# polarshield3_0b.net
KiCad netlist of a schematic drawn in EAGLE
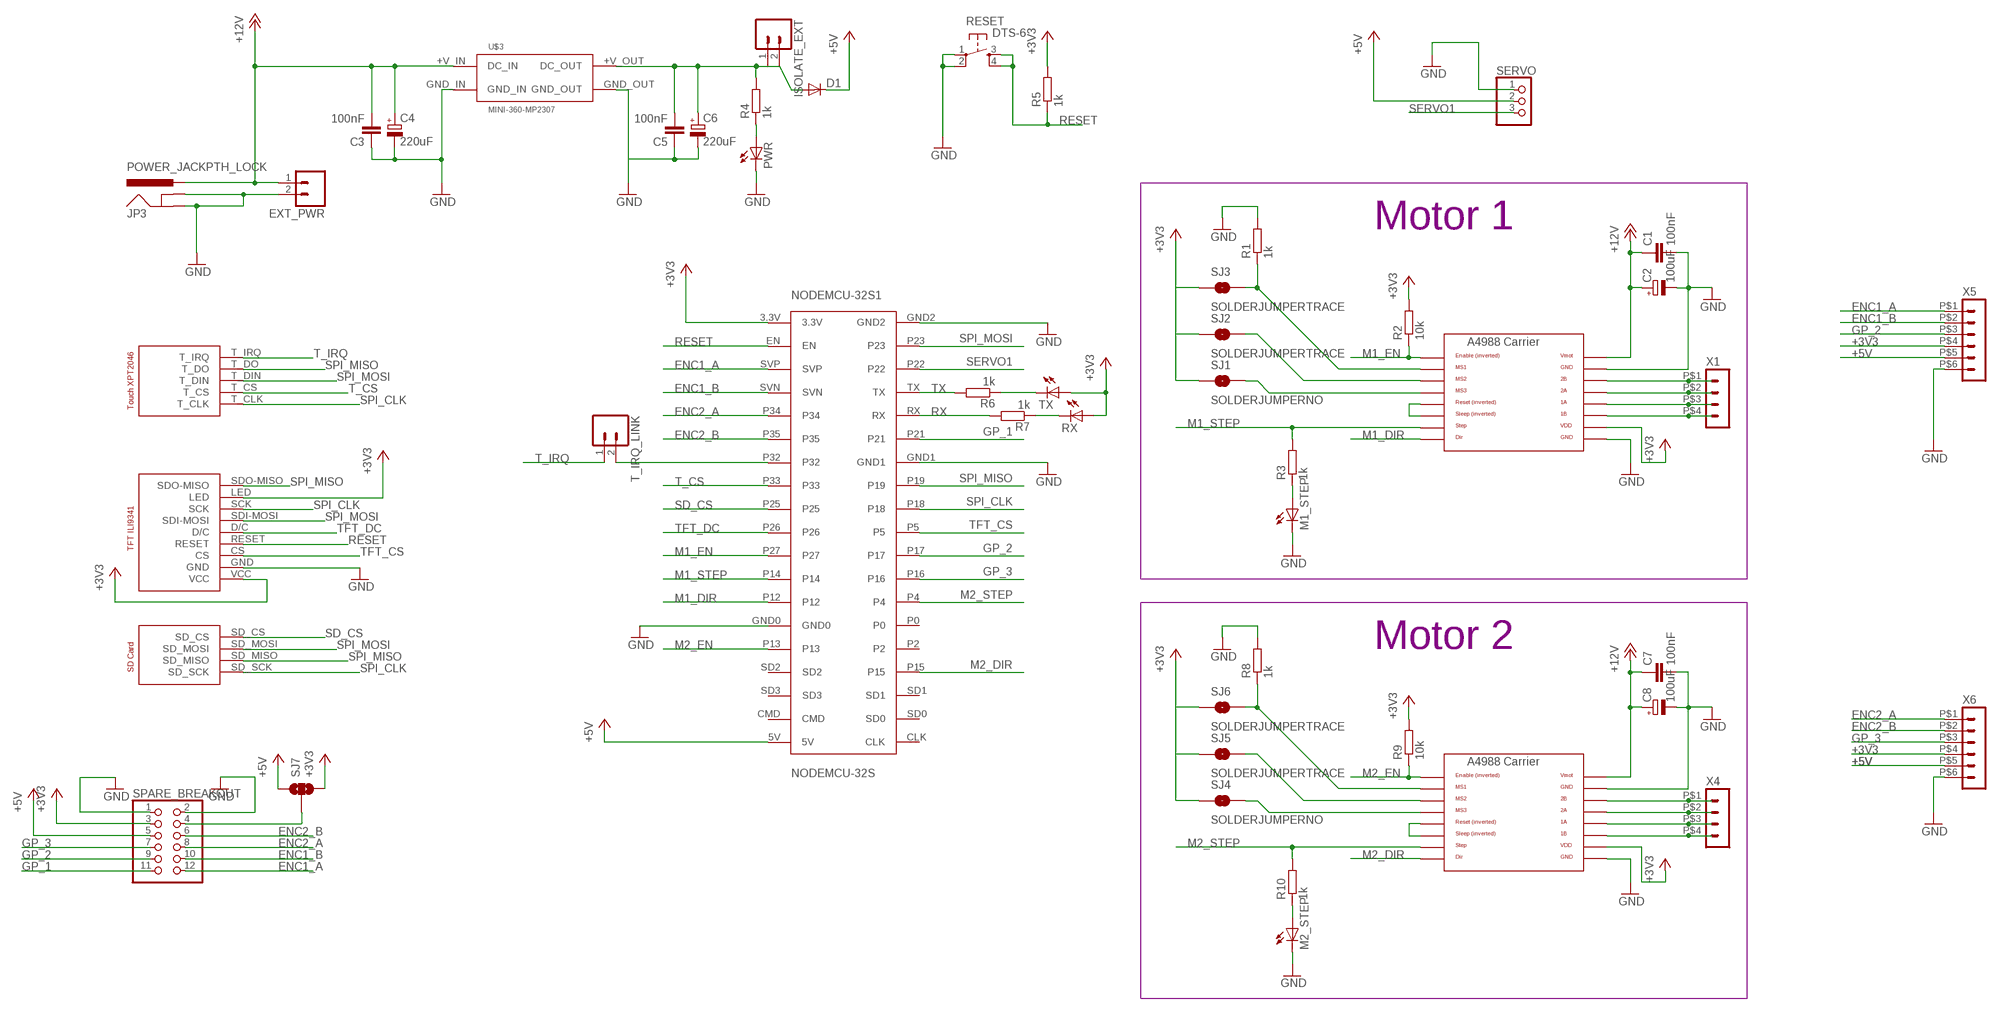
[diagram p0: schematic, sheet 1]

(export (version "E")
  (design (tool "Eeschema 10.0.6"))
  (components
    (comp (ref "C1")
      (value "100nF")
      (footprint "eagle-import:C0805")
      (libsource (lib "eagle-import") (part "C-EUC0805"))
    )
    (comp (ref "C2")
      (value "100uF")
      (footprint "eagle-import:153CLV-0605")
      (libsource (lib "eagle-import") (part "CPOL-EU153CLV-0605"))
    )
    (comp (ref "C3")
      (value "100nF")
      (footprint "eagle-import:C0805")
      (libsource (lib "eagle-import") (part "C-EUC0805"))
    )
    (comp (ref "C4")
      (value "220uF")
      (footprint "eagle-import:153CLV-0605")
      (libsource (lib "eagle-import") (part "CPOL-EU153CLV-0605"))
    )
    (comp (ref "C5")
      (value "100nF")
      (footprint "eagle-import:C0805")
      (libsource (lib "eagle-import") (part "C-EUC0805"))
    )
    (comp (ref "C6")
      (value "220uF")
      (footprint "eagle-import:153CLV-0605")
      (libsource (lib "eagle-import") (part "CPOL-EU153CLV-0605"))
    )
    (comp (ref "C7")
      (value "100nF")
      (footprint "eagle-import:C0805")
      (libsource (lib "eagle-import") (part "C-EUC0805"))
    )
    (comp (ref "C8")
      (value "100uF")
      (footprint "eagle-import:153CLV-0605")
      (libsource (lib "eagle-import") (part "CPOL-EU153CLV-0605"))
    )
    (comp (ref "D1")
      (value "DIODE-DO214BA")
      (footprint "eagle-import:DO214BA")
      (libsource (lib "eagle-import") (part "DIODE-DO214BA"))
    )
    (comp (ref "EXT_PWR")
      (value "M02PTH")
      (footprint "eagle-import:1X02")
      (libsource (lib "eagle-import") (part "M02PTH"))
    )
    (comp (ref "ISOLATE_EXT")
      (value "M02PTH")
      (footprint "eagle-import:1X02")
      (libsource (lib "eagle-import") (part "M02PTH"))
    )
    (comp (ref "JP3")
      (value "POWER_JACKPTH_LOCK")
      (footprint "eagle-import:POWER_JACK_PTH_LOCK")
      (libsource (lib "eagle-import") (part "POWER_JACKPTH_LOCK"))
    )
    (comp (ref "M1_STEP")
      (value "LEDCHIPLED_0805")
      (footprint "eagle-import:CHIPLED_0805")
      (libsource (lib "eagle-import") (part "LEDCHIPLED_0805"))
    )
    (comp (ref "M2_STEP")
      (value "LEDCHIPLED_0805")
      (footprint "eagle-import:CHIPLED_0805")
      (libsource (lib "eagle-import") (part "LEDCHIPLED_0805"))
    )
    (comp (ref "MOTOR_1")
      (value "A4988BREAKOUT")
      (footprint "eagle-import:A4988BREAKOUT")
      (libsource (lib "eagle-import") (part "A4988BREAKOUT"))
    )
    (comp (ref "MOTOR_2")
      (value "A4988BREAKOUT")
      (footprint "eagle-import:A4988BREAKOUT")
      (libsource (lib "eagle-import") (part "A4988BREAKOUT"))
    )
    (comp (ref "NODEMCU-32S1")
      (value "NODEMCU-32S")
      (footprint "eagle-import:NODEMCU-32S")
      (libsource (lib "eagle-import") (part "NODEMCU-32S"))
    )
    (comp (ref "PWR")
      (value "LEDCHIPLED_0805")
      (footprint "eagle-import:CHIPLED_0805")
      (libsource (lib "eagle-import") (part "LEDCHIPLED_0805"))
    )
    (comp (ref "R1")
      (value "1k")
      (footprint "eagle-import:M0805")
      (libsource (lib "eagle-import") (part "R-EU_M0805"))
    )
    (comp (ref "R2")
      (value "10k")
      (footprint "eagle-import:M0805")
      (libsource (lib "eagle-import") (part "R-EU_M0805"))
    )
    (comp (ref "R3")
      (value "1k")
      (footprint "eagle-import:M0805")
      (libsource (lib "eagle-import") (part "R-EU_M0805"))
    )
    (comp (ref "R4")
      (value "1k")
      (footprint "eagle-import:M0805")
      (libsource (lib "eagle-import") (part "R-EU_M0805"))
    )
    (comp (ref "R5")
      (value "1k")
      (footprint "eagle-import:M0805")
      (libsource (lib "eagle-import") (part "R-EU_M0805"))
    )
    (comp (ref "R6")
      (value "1k")
      (footprint "eagle-import:M0805")
      (libsource (lib "eagle-import") (part "R-EU_M0805"))
    )
    (comp (ref "R7")
      (value "1k")
      (footprint "eagle-import:M0805")
      (libsource (lib "eagle-import") (part "R-EU_M0805"))
    )
    (comp (ref "R8")
      (value "1k")
      (footprint "eagle-import:M0805")
      (libsource (lib "eagle-import") (part "R-EU_M0805"))
    )
    (comp (ref "R9")
      (value "10k")
      (footprint "eagle-import:M0805")
      (libsource (lib "eagle-import") (part "R-EU_M0805"))
    )
    (comp (ref "R10")
      (value "1k")
      (footprint "eagle-import:M0805")
      (libsource (lib "eagle-import") (part "R-EU_M0805"))
    )
    (comp (ref "RESET")
      (value "DTS-6")
      (footprint "eagle-import:DTS-6")
      (libsource (lib "eagle-import") (part "DTS-6"))
    )
    (comp (ref "RX")
      (value "LEDCHIPLED_0805")
      (footprint "eagle-import:CHIPLED_0805")
      (libsource (lib "eagle-import") (part "LEDCHIPLED_0805"))
    )
    (comp (ref "SERVO")
      (value "PINHD-1X3/90")
      (footprint "eagle-import:1X03_90")
      (libsource (lib "eagle-import") (part "PINHD-1X3/90"))
    )
    (comp (ref "SJ1")
      (value "SOLDERJUMPERNO")
      (footprint "eagle-import:SJ_2S-NO")
      (libsource (lib "eagle-import") (part "SOLDERJUMPERNO"))
    )
    (comp (ref "SJ2")
      (value "SOLDERJUMPERTRACE")
      (footprint "eagle-import:SJ_2S-TRACE")
      (libsource (lib "eagle-import") (part "SOLDERJUMPERTRACE"))
    )
    (comp (ref "SJ3")
      (value "SOLDERJUMPERTRACE")
      (footprint "eagle-import:SJ_2S-TRACE")
      (libsource (lib "eagle-import") (part "SOLDERJUMPERTRACE"))
    )
    (comp (ref "SJ4")
      (value "SOLDERJUMPERNO")
      (footprint "eagle-import:SJ_2S-NO")
      (libsource (lib "eagle-import") (part "SOLDERJUMPERNO"))
    )
    (comp (ref "SJ5")
      (value "SOLDERJUMPERTRACE")
      (footprint "eagle-import:SJ_2S-TRACE")
      (libsource (lib "eagle-import") (part "SOLDERJUMPERTRACE"))
    )
    (comp (ref "SJ6")
      (value "SOLDERJUMPERTRACE")
      (footprint "eagle-import:SJ_2S-TRACE")
      (libsource (lib "eagle-import") (part "SOLDERJUMPERTRACE"))
    )
    (comp (ref "SJ7")
      (value "SOLDERJUMPER_2WAYPASTE1&2")
      (footprint "eagle-import:SJ_3_PASTE1&2")
      (libsource (lib "eagle-import") (part "SOLDERJUMPER_2WAYPASTE1&2"))
    )
    (comp (ref "SPARE_BREAKOUT")
      (value "PINHD-2X6")
      (footprint "eagle-import:2X06")
      (libsource (lib "eagle-import") (part "PINHD-2X6"))
    )
    (comp (ref "TX")
      (value "LEDCHIPLED_0805")
      (footprint "eagle-import:CHIPLED_0805")
      (libsource (lib "eagle-import") (part "LEDCHIPLED_0805"))
    )
    (comp (ref "T_IRQ_LINK")
      (value "M02PTH")
      (footprint "eagle-import:1X02")
      (libsource (lib "eagle-import") (part "M02PTH"))
    )
    (comp (ref "U$2")
      (value "2.4_TFT_SPI_TOUCH_SD")
      (footprint "eagle-import:2.4_TFT_SPI_TOUCH_SD")
      (libsource (lib "eagle-import") (part "2.4_TFT_SPI_TOUCH_SD"))
    )
    (comp (ref "U$3")
      (value "MINI-360-MP2307")
      (footprint "eagle-import:MINI-360-MP2307")
      (libsource (lib "eagle-import") (part "MINI-360-MP2307"))
    )
    (comp (ref "X1")
      (value "HEADER_POS4_43045-0401")
      (footprint "eagle-import:43045-0400")
      (libsource (lib "eagle-import") (part "HEADER_POS4_?43045-0401"))
    )
    (comp (ref "X4")
      (value "HEADER_POS4_43045-0401")
      (footprint "eagle-import:43045-0400")
      (libsource (lib "eagle-import") (part "HEADER_POS4_?43045-0401"))
    )
    (comp (ref "X5")
      (value "HEADER_POS6_43045-0600")
      (footprint "eagle-import:43045-0600")
      (libsource (lib "eagle-import") (part "HEADER_POS6_?43045-0600"))
    )
    (comp (ref "X6")
      (value "HEADER_POS6_43045-0600")
      (footprint "eagle-import:43045-0600")
      (libsource (lib "eagle-import") (part "HEADER_POS6_?43045-0600"))
    )
  )
  (nets
    (net (code "1") (name "+3V3") (class "Default")
      (node (ref "MOTOR_1") (pin "VDD") (pinfunction "VDD_VDD") (pintype "power_in"))
      (node (ref "MOTOR_2") (pin "VDD") (pinfunction "VDD_VDD") (pintype "power_in"))
      (node (ref "NODEMCU-32S1") (pin "3.3V") (pinfunction "3.3V_3.3V") (pintype "bidirectional"))
      (node (ref "R2") (pin "2") (pinfunction "2_2") (pintype "passive"))
      (node (ref "R5") (pin "2") (pinfunction "2_2") (pintype "passive"))
      (node (ref "R9") (pin "2") (pinfunction "2_2") (pintype "passive"))
      (node (ref "RX") (pin "A") (pinfunction "A_A") (pintype "passive"))
      (node (ref "SJ1") (pin "1") (pinfunction "1_1") (pintype "passive"))
      (node (ref "SJ2") (pin "1") (pinfunction "1_1") (pintype "passive"))
      (node (ref "SJ3") (pin "1") (pinfunction "1_1") (pintype "passive"))
      (node (ref "SJ4") (pin "1") (pinfunction "1_1") (pintype "passive"))
      (node (ref "SJ5") (pin "1") (pinfunction "1_1") (pintype "passive"))
      (node (ref "SJ6") (pin "1") (pinfunction "1_1") (pintype "passive"))
      (node (ref "SJ7") (pin "3") (pinfunction "3_3") (pintype "passive"))
      (node (ref "SPARE_BREAKOUT") (pin "3") (pinfunction "3_3") (pintype "passive"))
      (node (ref "TX") (pin "A") (pinfunction "A_A") (pintype "passive"))
      (node (ref "U$2") (pin "LED") (pinfunction "LED_LED") (pintype "bidirectional"))
      (node (ref "U$2") (pin "VCC") (pinfunction "VCC_VCC") (pintype "bidirectional"))
      (node (ref "X5") (pin "P$4") (pinfunction "4_P$4") (pintype "passive"))
      (node (ref "X6") (pin "P$4") (pinfunction "4_P$4") (pintype "passive"))
    )
    (net (code "2") (name "+5V") (class "Default")
      (node (ref "D1") (pin "C") (pinfunction "C_C") (pintype "passive"))
      (node (ref "NODEMCU-32S1") (pin "5V") (pinfunction "5V_5V") (pintype "bidirectional"))
      (node (ref "SERVO") (pin "2") (pinfunction "2_2") (pintype "passive"))
      (node (ref "SJ7") (pin "1") (pinfunction "1_1") (pintype "passive"))
      (node (ref "SPARE_BREAKOUT") (pin "5") (pinfunction "5_5") (pintype "passive"))
      (node (ref "X5") (pin "P$5") (pinfunction "5_P$5") (pintype "passive"))
      (node (ref "X6") (pin "P$5") (pinfunction "5_P$5") (pintype "passive"))
    )
    (net (code "3") (name "+12V") (class "Default")
      (node (ref "C1") (pin "1") (pinfunction "1_1") (pintype "passive"))
      (node (ref "C2") (pin "+") (pinfunction "+_+") (pintype "passive"))
      (node (ref "C3") (pin "2") (pinfunction "2_2") (pintype "passive"))
      (node (ref "C4") (pin "+") (pinfunction "+_+") (pintype "passive"))
      (node (ref "C7") (pin "1") (pinfunction "1_1") (pintype "passive"))
      (node (ref "C8") (pin "+") (pinfunction "+_+") (pintype "passive"))
      (node (ref "EXT_PWR") (pin "1") (pinfunction "1_1") (pintype "passive"))
      (node (ref "JP3") (pin "PWR") (pinfunction "PWR_PWR") (pintype "bidirectional"))
      (node (ref "MOTOR_1") (pin "VMOT") (pinfunction "VMOT_VMOT") (pintype "power_in"))
      (node (ref "MOTOR_2") (pin "VMOT") (pinfunction "VMOT_VMOT") (pintype "power_in"))
      (node (ref "U$3") (pin "+V_IN") (pinfunction "DC_IN_+V_IN") (pintype "bidirectional"))
    )
    (net (code "4") (name "/ENC1_A") (class "Default")
      (node (ref "NODEMCU-32S1") (pin "SVP") (pinfunction "SVP_SVP") (pintype "bidirectional"))
      (node (ref "SPARE_BREAKOUT") (pin "12") (pinfunction "12_12") (pintype "passive"))
      (node (ref "X5") (pin "P$1") (pinfunction "1_P$1") (pintype "passive"))
    )
    (net (code "5") (name "/ENC1_B") (class "Default")
      (node (ref "NODEMCU-32S1") (pin "SVN") (pinfunction "SVN_SVN") (pintype "bidirectional"))
      (node (ref "SPARE_BREAKOUT") (pin "10") (pinfunction "10_10") (pintype "passive"))
      (node (ref "X5") (pin "P$2") (pinfunction "2_P$2") (pintype "passive"))
    )
    (net (code "6") (name "/ENC2_A") (class "Default")
      (node (ref "NODEMCU-32S1") (pin "P34") (pinfunction "P34_P34") (pintype "bidirectional"))
      (node (ref "SPARE_BREAKOUT") (pin "8") (pinfunction "8_8") (pintype "passive"))
      (node (ref "X6") (pin "P$1") (pinfunction "1_P$1") (pintype "passive"))
    )
    (net (code "7") (name "/ENC2_B") (class "Default")
      (node (ref "NODEMCU-32S1") (pin "P35") (pinfunction "P35_P35") (pintype "bidirectional"))
      (node (ref "SPARE_BREAKOUT") (pin "6") (pinfunction "6_6") (pintype "passive"))
      (node (ref "X6") (pin "P$2") (pinfunction "2_P$2") (pintype "passive"))
    )
    (net (code "8") (name "/GP_1") (class "Default")
      (node (ref "NODEMCU-32S1") (pin "P21") (pinfunction "P21_P21") (pintype "bidirectional"))
      (node (ref "SPARE_BREAKOUT") (pin "11") (pinfunction "11_11") (pintype "passive"))
    )
    (net (code "9") (name "/GP_2") (class "Default")
      (node (ref "NODEMCU-32S1") (pin "P17") (pinfunction "P17_P17") (pintype "bidirectional"))
      (node (ref "SPARE_BREAKOUT") (pin "9") (pinfunction "9_9") (pintype "passive"))
      (node (ref "X5") (pin "P$3") (pinfunction "3_P$3") (pintype "passive"))
    )
    (net (code "10") (name "/GP_3") (class "Default")
      (node (ref "NODEMCU-32S1") (pin "P16") (pinfunction "P16_P16") (pintype "bidirectional"))
      (node (ref "SPARE_BREAKOUT") (pin "7") (pinfunction "7_7") (pintype "passive"))
      (node (ref "X6") (pin "P$3") (pinfunction "3_P$3") (pintype "passive"))
    )
    (net (code "11") (name "/M1_DIR") (class "Default")
      (node (ref "MOTOR_1") (pin "DIR") (pinfunction "DIR_DIR") (pintype "input"))
      (node (ref "NODEMCU-32S1") (pin "P12") (pinfunction "P12_P12") (pintype "bidirectional"))
    )
    (net (code "12") (name "/M1_EN") (class "Default")
      (node (ref "MOTOR_1") (pin "EN") (pinfunction "EN_EN") (pintype "input"))
      (node (ref "NODEMCU-32S1") (pin "P27") (pinfunction "P27_P27") (pintype "bidirectional"))
      (node (ref "R2") (pin "1") (pinfunction "1_1") (pintype "passive"))
    )
    (net (code "13") (name "/M1_STEP") (class "Default")
      (node (ref "MOTOR_1") (pin "STEP") (pinfunction "STEP_STEP") (pintype "input"))
      (node (ref "NODEMCU-32S1") (pin "P14") (pinfunction "P14_P14") (pintype "bidirectional"))
      (node (ref "R3") (pin "2") (pinfunction "2_2") (pintype "passive"))
    )
    (net (code "14") (name "/M2_DIR") (class "Default")
      (node (ref "MOTOR_2") (pin "DIR") (pinfunction "DIR_DIR") (pintype "input"))
      (node (ref "NODEMCU-32S1") (pin "P15") (pinfunction "P15_P15") (pintype "bidirectional"))
    )
    (net (code "15") (name "/M2_EN") (class "Default")
      (node (ref "MOTOR_2") (pin "EN") (pinfunction "EN_EN") (pintype "input"))
      (node (ref "NODEMCU-32S1") (pin "P13") (pinfunction "P13_P13") (pintype "bidirectional"))
      (node (ref "R9") (pin "1") (pinfunction "1_1") (pintype "passive"))
    )
    (net (code "16") (name "/M2_STEP") (class "Default")
      (node (ref "MOTOR_2") (pin "STEP") (pinfunction "STEP_STEP") (pintype "input"))
      (node (ref "NODEMCU-32S1") (pin "P4") (pinfunction "P4_P4") (pintype "bidirectional"))
      (node (ref "R10") (pin "2") (pinfunction "2_2") (pintype "passive"))
    )
    (net (code "17") (name "/RESET") (class "Default")
      (node (ref "NODEMCU-32S1") (pin "EN") (pinfunction "EN_EN") (pintype "bidirectional"))
      (node (ref "R5") (pin "1") (pinfunction "1_1") (pintype "passive"))
      (node (ref "RESET") (pin "3") (pinfunction "3_3") (pintype "passive"))
      (node (ref "RESET") (pin "4") (pinfunction "4_4") (pintype "passive"))
      (node (ref "U$2") (pin "RESET") (pinfunction "RESET_RESET") (pintype "bidirectional"))
    )
    (net (code "18") (name "/RX") (class "Default")
      (node (ref "NODEMCU-32S1") (pin "RX") (pinfunction "RX_RX") (pintype "bidirectional"))
      (node (ref "R7") (pin "2") (pinfunction "2_2") (pintype "passive"))
    )
    (net (code "19") (name "/SD_CS") (class "Default")
      (node (ref "NODEMCU-32S1") (pin "P25") (pinfunction "P25_P25") (pintype "bidirectional"))
      (node (ref "U$2") (pin "SD_CS") (pinfunction "SD_CS_SD_CS") (pintype "bidirectional"))
    )
    (net (code "20") (name "/SERVO1") (class "Default")
      (node (ref "NODEMCU-32S1") (pin "P22") (pinfunction "P22_P22") (pintype "bidirectional"))
      (node (ref "SERVO") (pin "3") (pinfunction "3_3") (pintype "passive"))
    )
    (net (code "21") (name "/SPI_CLK") (class "Default")
      (node (ref "NODEMCU-32S1") (pin "P18") (pinfunction "P18_P18") (pintype "bidirectional"))
      (node (ref "U$2") (pin "SCK") (pinfunction "SCK_SCK") (pintype "bidirectional"))
      (node (ref "U$2") (pin "SD_SCK") (pinfunction "SD_SCK_SD_SCK") (pintype "bidirectional"))
      (node (ref "U$2") (pin "T_CLK") (pinfunction "T_CLK_T_CLK") (pintype "input"))
    )
    (net (code "22") (name "/SPI_MISO") (class "Default")
      (node (ref "NODEMCU-32S1") (pin "P19") (pinfunction "P19_P19") (pintype "bidirectional"))
      (node (ref "U$2") (pin "SDO-MISO") (pinfunction "SDO-MISO_SDO-MISO") (pintype "bidirectional"))
      (node (ref "U$2") (pin "SD_MISO") (pinfunction "SD_MISO_SD_MISO") (pintype "bidirectional"))
      (node (ref "U$2") (pin "T_DO") (pinfunction "T_DO_T_DO") (pintype "output"))
    )
    (net (code "23") (name "/SPI_MOSI") (class "Default")
      (node (ref "NODEMCU-32S1") (pin "P23") (pinfunction "P23_P23") (pintype "bidirectional"))
      (node (ref "U$2") (pin "SDI-MOSI") (pinfunction "SDI-MOSI_SDI-MOSI") (pintype "bidirectional"))
      (node (ref "U$2") (pin "SD_MOSI") (pinfunction "SD_MOSI_SD_MOSI") (pintype "bidirectional"))
      (node (ref "U$2") (pin "T_DIN") (pinfunction "T_DIN_T_DIN") (pintype "input"))
    )
    (net (code "24") (name "/TFT_CS") (class "Default")
      (node (ref "NODEMCU-32S1") (pin "P5") (pinfunction "P5_P5") (pintype "bidirectional"))
      (node (ref "U$2") (pin "CS") (pinfunction "CS_CS") (pintype "bidirectional"))
    )
    (net (code "25") (name "/TFT_DC") (class "Default")
      (node (ref "NODEMCU-32S1") (pin "P26") (pinfunction "P26_P26") (pintype "bidirectional"))
      (node (ref "U$2") (pin "D/C") (pinfunction "D/C_D/C") (pintype "bidirectional"))
    )
    (net (code "26") (name "/TX") (class "Default")
      (node (ref "NODEMCU-32S1") (pin "TX") (pinfunction "TX_TX") (pintype "bidirectional"))
      (node (ref "R6") (pin "2") (pinfunction "2_2") (pintype "passive"))
    )
    (net (code "27") (name "/T_CS") (class "Default")
      (node (ref "NODEMCU-32S1") (pin "P33") (pinfunction "P33_P33") (pintype "bidirectional"))
      (node (ref "U$2") (pin "T_CS") (pinfunction "T_CS_T_CS") (pintype "output"))
    )
    (net (code "28") (name "/T_IRQ") (class "Default")
      (node (ref "T_IRQ_LINK") (pin "1") (pinfunction "1_1") (pintype "passive"))
      (node (ref "U$2") (pin "T_IRQ") (pinfunction "T_IRQ_T_IRQ") (pintype "output"))
    )
    (net (code "29") (name "GND") (class "Default")
      (node (ref "C1") (pin "2") (pinfunction "2_2") (pintype "passive"))
      (node (ref "C2") (pin "-") (pinfunction "-_-") (pintype "passive"))
      (node (ref "C3") (pin "1") (pinfunction "1_1") (pintype "passive"))
      (node (ref "C4") (pin "-") (pinfunction "-_-") (pintype "passive"))
      (node (ref "C5") (pin "1") (pinfunction "1_1") (pintype "passive"))
      (node (ref "C6") (pin "-") (pinfunction "-_-") (pintype "passive"))
      (node (ref "C7") (pin "2") (pinfunction "2_2") (pintype "passive"))
      (node (ref "C8") (pin "-") (pinfunction "-_-") (pintype "passive"))
      (node (ref "EXT_PWR") (pin "2") (pinfunction "2_2") (pintype "passive"))
      (node (ref "JP3") (pin "GND") (pinfunction "GND_GND") (pintype "bidirectional"))
      (node (ref "JP3") (pin "GNDBREAK") (pinfunction "GNDBREAK_GNDBREAK") (pintype "bidirectional"))
      (node (ref "M1_STEP") (pin "C") (pinfunction "C_C") (pintype "passive"))
      (node (ref "M2_STEP") (pin "C") (pinfunction "C_C") (pintype "passive"))
      (node (ref "MOTOR_1") (pin "GND") (pinfunction "GND_GND") (pintype "power_in"))
      (node (ref "MOTOR_1") (pin "GND@0") (pinfunction "GND_GND@0") (pintype "power_in"))
      (node (ref "MOTOR_2") (pin "GND") (pinfunction "GND_GND") (pintype "power_in"))
      (node (ref "MOTOR_2") (pin "GND@0") (pinfunction "GND_GND@0") (pintype "power_in"))
      (node (ref "NODEMCU-32S1") (pin "GND0") (pinfunction "GND0_GND0") (pintype "bidirectional"))
      (node (ref "NODEMCU-32S1") (pin "GND1") (pinfunction "GND1_GND1") (pintype "bidirectional"))
      (node (ref "NODEMCU-32S1") (pin "GND2") (pinfunction "GND2_GND2") (pintype "bidirectional"))
      (node (ref "PWR") (pin "C") (pinfunction "C_C") (pintype "passive"))
      (node (ref "R1") (pin "2") (pinfunction "2_2") (pintype "passive"))
      (node (ref "R8") (pin "2") (pinfunction "2_2") (pintype "passive"))
      (node (ref "RESET") (pin "1") (pinfunction "1_1") (pintype "passive"))
      (node (ref "RESET") (pin "2") (pinfunction "2_2") (pintype "passive"))
      (node (ref "SERVO") (pin "1") (pinfunction "1_1") (pintype "passive"))
      (node (ref "SPARE_BREAKOUT") (pin "1") (pinfunction "1_1") (pintype "passive"))
      (node (ref "SPARE_BREAKOUT") (pin "2") (pinfunction "2_2") (pintype "passive"))
      (node (ref "U$2") (pin "GND") (pinfunction "GND_GND") (pintype "bidirectional"))
      (node (ref "U$3") (pin "GND_IN") (pinfunction "GND_IN_GND_IN") (pintype "bidirectional"))
      (node (ref "U$3") (pin "GND_OUT") (pinfunction "GND_OUT_GND_OUT") (pintype "bidirectional"))
      (node (ref "X5") (pin "P$6") (pinfunction "6_P$6") (pintype "passive"))
      (node (ref "X6") (pin "P$6") (pinfunction "6_P$6") (pintype "passive"))
    )
    (net (code "30") (name "Net-(M1_STEP-PadA)") (class "Default")
      (node (ref "M1_STEP") (pin "A") (pinfunction "A_A") (pintype "passive"))
      (node (ref "R3") (pin "1") (pinfunction "1_1") (pintype "passive"))
    )
    (net (code "31") (name "Net-(M2_STEP-PadA)") (class "Default")
      (node (ref "M2_STEP") (pin "A") (pinfunction "A_A") (pintype "passive"))
      (node (ref "R10") (pin "1") (pinfunction "1_1") (pintype "passive"))
    )
    (net (code "32") (name "Net-(MOTOR_1-PadMS1)") (class "Default")
      (node (ref "MOTOR_1") (pin "MS1") (pinfunction "MS1_MS1") (pintype "input"))
      (node (ref "R1") (pin "1") (pinfunction "1_1") (pintype "passive"))
      (node (ref "SJ3") (pin "2") (pinfunction "2_2") (pintype "passive"))
    )
    (net (code "33") (name "Net-(MOTOR_1-PadMS2)") (class "Default")
      (node (ref "MOTOR_1") (pin "MS2") (pinfunction "MS2_MS2") (pintype "input"))
      (node (ref "SJ2") (pin "2") (pinfunction "2_2") (pintype "passive"))
    )
    (net (code "34") (name "Net-(MOTOR_1-PadMS3)") (class "Default")
      (node (ref "MOTOR_1") (pin "MS3") (pinfunction "MS3_MS3") (pintype "input"))
      (node (ref "SJ1") (pin "2") (pinfunction "2_2") (pintype "passive"))
    )
    (net (code "35") (name "Net-(MOTOR_1-SLEEP)") (class "Default")
      (node (ref "MOTOR_1") (pin "RST") (pinfunction "RST_RST") (pintype "input"))
      (node (ref "MOTOR_1") (pin "SLP") (pinfunction "SLEEP_SLP") (pintype "input"))
    )
    (net (code "36") (name "Net-(MOTOR_2-PadMS1)") (class "Default")
      (node (ref "MOTOR_2") (pin "MS1") (pinfunction "MS1_MS1") (pintype "input"))
      (node (ref "R8") (pin "1") (pinfunction "1_1") (pintype "passive"))
      (node (ref "SJ6") (pin "2") (pinfunction "2_2") (pintype "passive"))
    )
    (net (code "37") (name "Net-(MOTOR_2-PadMS2)") (class "Default")
      (node (ref "MOTOR_2") (pin "MS2") (pinfunction "MS2_MS2") (pintype "input"))
      (node (ref "SJ5") (pin "2") (pinfunction "2_2") (pintype "passive"))
    )
    (net (code "38") (name "Net-(MOTOR_2-PadMS3)") (class "Default")
      (node (ref "MOTOR_2") (pin "MS3") (pinfunction "MS3_MS3") (pintype "input"))
      (node (ref "SJ4") (pin "2") (pinfunction "2_2") (pintype "passive"))
    )
    (net (code "39") (name "Net-(MOTOR_2-SLEEP)") (class "Default")
      (node (ref "MOTOR_2") (pin "RST") (pinfunction "RST_RST") (pintype "input"))
      (node (ref "MOTOR_2") (pin "SLP") (pinfunction "SLEEP_SLP") (pintype "input"))
    )
    (net (code "40") (name "Net-(NODEMCU-32S1-PadP32)") (class "Default")
      (node (ref "NODEMCU-32S1") (pin "P32") (pinfunction "P32_P32") (pintype "bidirectional"))
      (node (ref "T_IRQ_LINK") (pin "2") (pinfunction "2_2") (pintype "passive"))
    )
    (net (code "41") (name "Net-(PWR-PadA)") (class "Default")
      (node (ref "PWR") (pin "A") (pinfunction "A_A") (pintype "passive"))
      (node (ref "R4") (pin "1") (pinfunction "1_1") (pintype "passive"))
    )
    (net (code "42") (name "Net-(R6-Pad1)") (class "Default")
      (node (ref "R6") (pin "1") (pinfunction "1_1") (pintype "passive"))
      (node (ref "TX") (pin "C") (pinfunction "C_C") (pintype "passive"))
    )
    (net (code "43") (name "Net-(R7-Pad1)") (class "Default")
      (node (ref "R7") (pin "1") (pinfunction "1_1") (pintype "passive"))
      (node (ref "RX") (pin "C") (pinfunction "C_C") (pintype "passive"))
    )
    (net (code "44") (name "Net-(SJ7-Pad2)") (class "Default")
      (node (ref "SJ7") (pin "2") (pinfunction "2_2") (pintype "passive"))
      (node (ref "SPARE_BREAKOUT") (pin "4") (pinfunction "4_4") (pintype "passive"))
    )
    (net (code "45") (name "Net-(U$3-DC_OUT)") (class "Default")
      (node (ref "C5") (pin "2") (pinfunction "2_2") (pintype "passive"))
      (node (ref "C6") (pin "+") (pinfunction "+_+") (pintype "passive"))
      (node (ref "D1") (pin "A") (pinfunction "A_A") (pintype "passive"))
      (node (ref "ISOLATE_EXT") (pin "1") (pinfunction "1_1") (pintype "passive"))
      (node (ref "ISOLATE_EXT") (pin "2") (pinfunction "2_2") (pintype "passive"))
      (node (ref "R4") (pin "2") (pinfunction "2_2") (pintype "passive"))
      (node (ref "U$3") (pin "+V_OUT") (pinfunction "DC_OUT_+V_OUT") (pintype "bidirectional"))
    )
    (net (code "46") (name "Net-(X1-1)") (class "Default")
      (node (ref "MOTOR_1") (pin "2B") (pinfunction "2B_2B") (pintype "output"))
      (node (ref "X1") (pin "P$1") (pinfunction "1_P$1") (pintype "passive"))
    )
    (net (code "47") (name "Net-(X1-2)") (class "Default")
      (node (ref "MOTOR_1") (pin "2A") (pinfunction "2A_2A") (pintype "output"))
      (node (ref "X1") (pin "P$2") (pinfunction "2_P$2") (pintype "passive"))
    )
    (net (code "48") (name "Net-(X1-3)") (class "Default")
      (node (ref "MOTOR_1") (pin "1A") (pinfunction "1A_1A") (pintype "output"))
      (node (ref "X1") (pin "P$3") (pinfunction "3_P$3") (pintype "passive"))
    )
    (net (code "49") (name "Net-(X1-4)") (class "Default")
      (node (ref "MOTOR_1") (pin "1B") (pinfunction "1B_1B") (pintype "output"))
      (node (ref "X1") (pin "P$4") (pinfunction "4_P$4") (pintype "passive"))
    )
    (net (code "50") (name "Net-(X4-1)") (class "Default")
      (node (ref "MOTOR_2") (pin "2B") (pinfunction "2B_2B") (pintype "output"))
      (node (ref "X4") (pin "P$1") (pinfunction "1_P$1") (pintype "passive"))
    )
    (net (code "51") (name "Net-(X4-2)") (class "Default")
      (node (ref "MOTOR_2") (pin "2A") (pinfunction "2A_2A") (pintype "output"))
      (node (ref "X4") (pin "P$2") (pinfunction "2_P$2") (pintype "passive"))
    )
    (net (code "52") (name "Net-(X4-3)") (class "Default")
      (node (ref "MOTOR_2") (pin "1A") (pinfunction "1A_1A") (pintype "output"))
      (node (ref "X4") (pin "P$3") (pinfunction "3_P$3") (pintype "passive"))
    )
    (net (code "53") (name "Net-(X4-4)") (class "Default")
      (node (ref "MOTOR_2") (pin "1B") (pinfunction "1B_1B") (pintype "output"))
      (node (ref "X4") (pin "P$4") (pinfunction "4_P$4") (pintype "passive"))
    )
    (net (code "54") (name "unconnected-(NODEMCU-32S1-PadCLK)") (class "Default")
      (node (ref "NODEMCU-32S1") (pin "CLK") (pinfunction "CLK_CLK") (pintype "bidirectional"))
    )
    (net (code "55") (name "unconnected-(NODEMCU-32S1-PadCMD)") (class "Default")
      (node (ref "NODEMCU-32S1") (pin "CMD") (pinfunction "CMD_CMD") (pintype "bidirectional"))
    )
    (net (code "56") (name "unconnected-(NODEMCU-32S1-PadP0)") (class "Default")
      (node (ref "NODEMCU-32S1") (pin "P0") (pinfunction "P0_P0") (pintype "bidirectional"))
    )
    (net (code "57") (name "unconnected-(NODEMCU-32S1-PadP2)") (class "Default")
      (node (ref "NODEMCU-32S1") (pin "P2") (pinfunction "P2_P2") (pintype "bidirectional"))
    )
    (net (code "58") (name "unconnected-(NODEMCU-32S1-PadSD0)") (class "Default")
      (node (ref "NODEMCU-32S1") (pin "SD0") (pinfunction "SD0_SD0") (pintype "bidirectional"))
    )
    (net (code "59") (name "unconnected-(NODEMCU-32S1-PadSD1)") (class "Default")
      (node (ref "NODEMCU-32S1") (pin "SD1") (pinfunction "SD1_SD1") (pintype "bidirectional"))
    )
    (net (code "60") (name "unconnected-(NODEMCU-32S1-PadSD2)") (class "Default")
      (node (ref "NODEMCU-32S1") (pin "SD2") (pinfunction "SD2_SD2") (pintype "bidirectional"))
    )
    (net (code "61") (name "unconnected-(NODEMCU-32S1-PadSD3)") (class "Default")
      (node (ref "NODEMCU-32S1") (pin "SD3") (pinfunction "SD3_SD3") (pintype "bidirectional"))
    )
  )
)
